# Linear_Regulator.net
KiCad netlist of a schematic drawn in Altium Designer
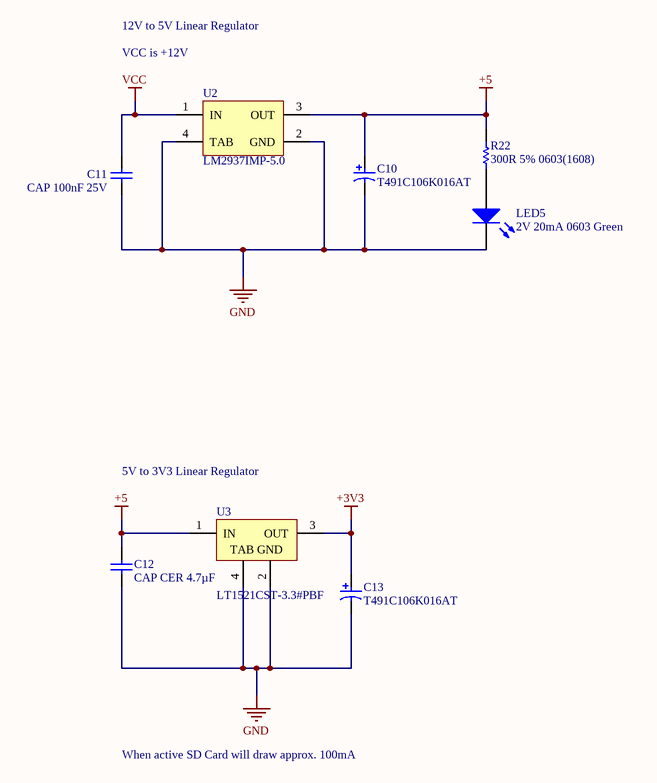
[diagram p0: Linear Regulator.SchDoc]

(export (version "E")
  (design (tool "Eeschema 10.0.6"))
  (components
    (comp (ref "C10")
      (value "T491C106K016AT")
      (footprint "KEMT-T491-C_L")
      (description "Tantalum Capacitor, 10 uF, +/- 10%, 16 V, -55 to 125 degC, 2-Pin SMD (T491-C), RoHS, Tape and Reel")
      (fields (field (name "VOLTAGE") "16VDC") (field (name "MANUFACTURER") "Kemet"))
      (libsource (lib "Altium Content Vault") (part "CAP-P-2"))
    )
    (comp (ref "C11")
      (value "CAP 100nF 25V")
      (footprint "CAPC0603(1608)100_M")
      (description "CAP 100nF 25V ±10% 0603 (1608 Metric) Thickness 1mm SMD")
      (fields (field (name "TOLERANCE") "Â±10%"))
      (libsource (lib "Altium Content Vault") (part "CAP"))
    )
    (comp (ref "C12")
      (value "CAP CER 4.7µF")
      (footprint "CAPC1608X90X35NL10T15")
      (description "GRM188R61E475KE11D")
      (fields (field (name "MANUFACTURER") "Murata"))
      (libsource (lib "Altium Content Vault") (part "CAP"))
    )
    (comp (ref "C13")
      (value "T491C106K016AT")
      (footprint "KEMT-T491-C_L")
      (description "Tantalum Capacitor, 10 uF, +/- 10%, 16 V, -55 to 125 degC, 2-Pin SMD (T491-C), RoHS, Tape and Reel")
      (fields (field (name "VOLTAGE") "16VDC") (field (name "MANUFACTURER") "Kemet"))
      (libsource (lib "Altium Content Vault") (part "CAP-P-2"))
    )
    (comp (ref "LED5")
      (value "2V 20mA 0603 Green")
      (footprint "LITE-ON-LTST-C191KRKT-2_V")
      (description "Chip LED, Green, 574 nm, 40 pF, -55 to 85 degC, 2-Pin SMD, RoHS, Tape and Reel")
      (fields (field (name "MANUFACTURER") "Lite-On"))
      (libsource (lib "Altium Content Vault") (part "LED-AK-2"))
    )
    (comp (ref "R22")
      (value "300R 5% 0603(1608)")
      (footprint "RESC0603(1608)_N")
      (description "300R 0.1W 5% 0603 (1608 Metric)  SMD")
      (fields (field (name "TOLERANCE") "5 %") (field (name "POWER") "0.1 W"))
      (libsource (lib "Altium Content Vault") (part "RES"))
    )
    (comp (ref "U2")
      (value "LM2937IMP-5.0")
      (footprint "DCY0004A_N")
      (description "500 mA Low Dropout Regulator, 4-pin SOT-223")
      (fields (field (name "MANUFACTURER") "Texas Instruments"))
      (libsource (lib "Altium Content Vault") (part "PM-REG-LM2940-TO4"))
    )
    (comp (ref "U3")
      (value "LT1521CST-3.3#PBF")
      (footprint "LT-ST-3-SOT-223_N")
      (fields (field (name "MANUFACTURER") "Linear Technology"))
      (libsource (lib "Altium Content Vault") (part "LT-LT1XXXX-ST-3X"))
    )
  )
  (nets
    (net (code "1") (name "+3V3") (class "Default")
      (node (ref "C13") (pin "1") (pinfunction "1_1") (pintype "passive"))
      (node (ref "U3") (pin "3") (pinfunction "OUT_3") (pintype "power_in"))
    )
    (net (code "2") (name "+5") (class "Default")
      (node (ref "C10") (pin "1") (pinfunction "1_1") (pintype "passive"))
      (node (ref "C12") (pin "2") (pinfunction "2_2") (pintype "passive"))
      (node (ref "R22") (pin "2") (pinfunction "2_2") (pintype "passive"))
      (node (ref "U2") (pin "3") (pinfunction "OUT_3") (pintype "power_in"))
      (node (ref "U3") (pin "1") (pinfunction "IN_1") (pintype "power_in"))
    )
    (net (code "3") (name "GND") (class "Default")
      (node (ref "C10") (pin "2") (pinfunction "2_2") (pintype "passive"))
      (node (ref "C11") (pin "1") (pinfunction "1_1") (pintype "passive"))
      (node (ref "C12") (pin "1") (pinfunction "1_1") (pintype "passive"))
      (node (ref "C13") (pin "2") (pinfunction "2_2") (pintype "passive"))
      (node (ref "LED5") (pin "2") (pinfunction "K_2") (pintype "passive"))
      (node (ref "U2") (pin "2") (pinfunction "GND_2") (pintype "power_in"))
      (node (ref "U2") (pin "4") (pinfunction "TAB_4") (pintype "power_in"))
      (node (ref "U3") (pin "2") (pinfunction "GND_2") (pintype "power_in"))
      (node (ref "U3") (pin "4") (pinfunction "TAB_4") (pintype "power_in"))
    )
    (net (code "4") (name "Net-(LED5-A)") (class "Default")
      (node (ref "LED5") (pin "1") (pinfunction "A_1") (pintype "passive"))
      (node (ref "R22") (pin "1") (pinfunction "1_1") (pintype "passive"))
    )
    (net (code "5") (name "VCC") (class "Default")
      (node (ref "C11") (pin "2") (pinfunction "2_2") (pintype "passive"))
      (node (ref "U2") (pin "1") (pinfunction "IN_1") (pintype "power_in"))
    )
  )
)
